# MOTOR_DRIVER_2.net
KiCad netlist of a schematic drawn in Altium Designer
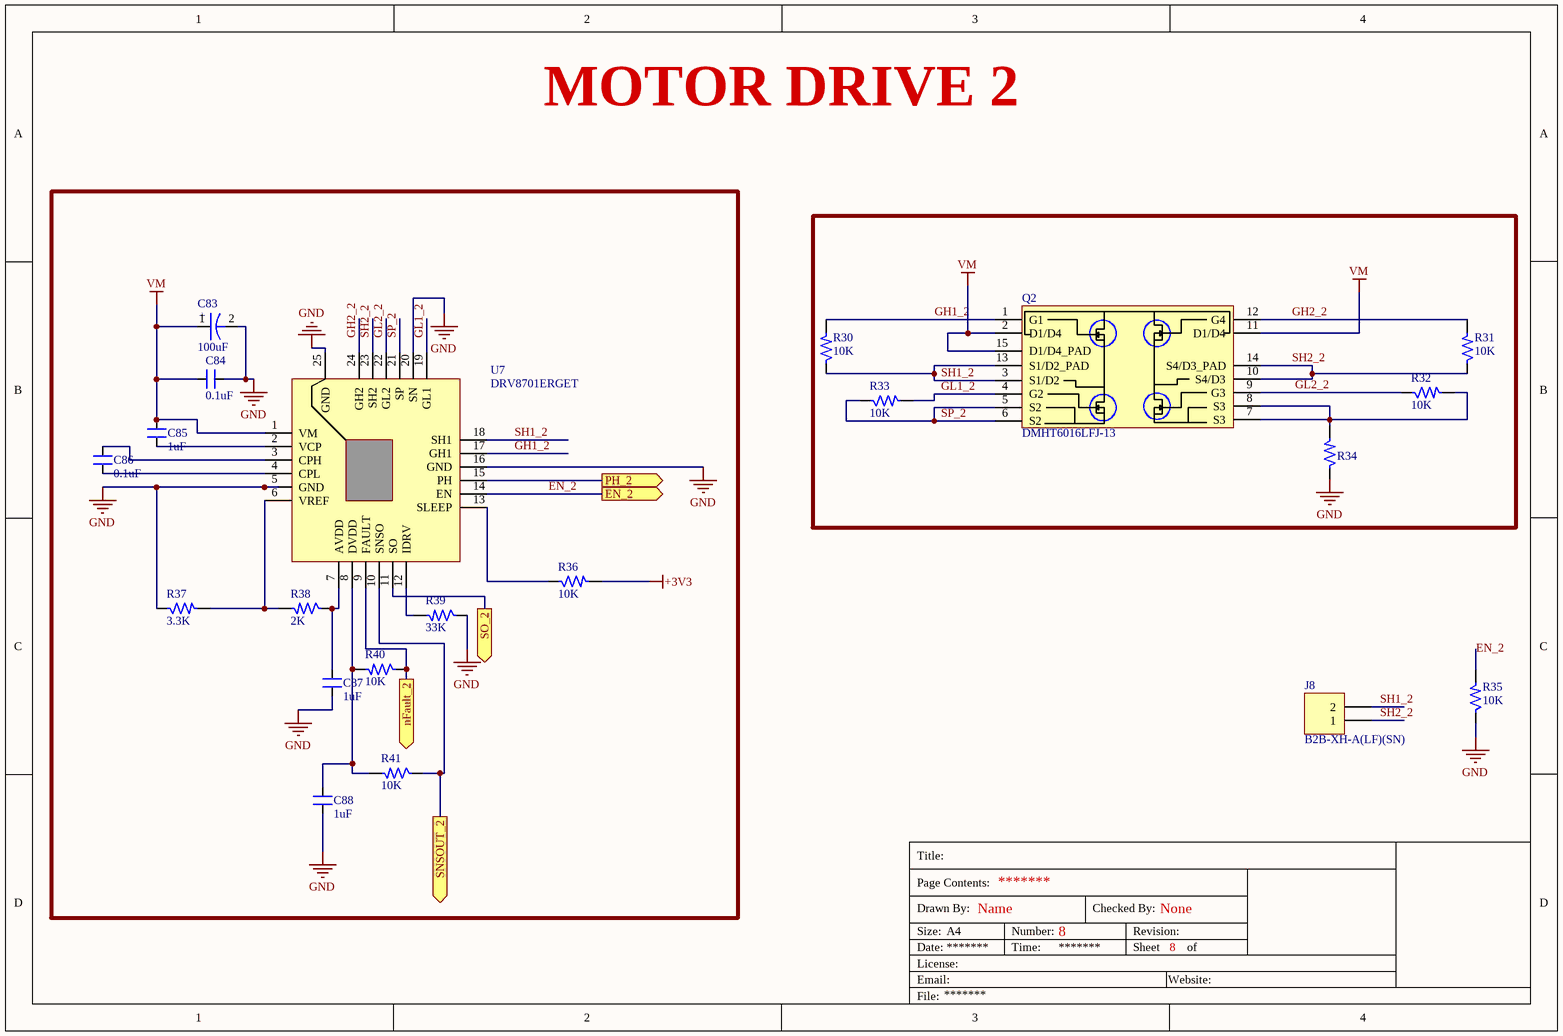
[diagram p0: MOTOR DRIVER 2.SchDoc]

(export (version "E")
  (design (tool "Eeschema 10.0.6"))
  (components
    (comp (ref "C83")
      (value "100uF")
      (footprint "ACAP_P236_D305_H303_RAD")
      (description "100µF 25V Aluminum Electrolytic Capacitors Radial, Can - SMD 1000 Hrs @ 105°C")
      (fields
        (field (name "MANUFACTURER") "Nichicon")
        (field (name "MANUFACTURER PART NUMBER") "UWT1E101MCL1GS")
      )
      (libsource (lib "ESTEEMPCBLIB") (part "CAP-P_100uF-25V-20%-RAD"))
    )
    (comp (ref "C84")
      (value "0.1uF")
      (footprint "CAP_0805")
      (description "0.1µF ±5% 50V Ceramic Capacitor X7R 0805 (2012 Metric)")
      (fields
        (field (name "MANUFACTURER") "AVX Corporation")
        (field (name "MANUFACTURER PART NUMBER") "08055C104JAT4A")
      )
      (libsource (lib "ESTEEMPCBLIB") (part "CAP_0.1uF-50V-5%-0805"))
    )
    (comp (ref "C85")
      (value "1uF")
      (footprint "CAP_0805")
      (description "1µF ±5% 50V Ceramic Capacitor X7R 0805 (2012 Metric)")
      (fields
        (field (name "MANUFACTURER") "Samsung")
        (field (name "MANUFACTURER PART NUMBER") "CC0805JKX7R9BB105")
      )
      (libsource (lib "ESTEEMPCBLIB") (part "CAP_1uF-50V-5%-0805"))
    )
    (comp (ref "C86")
      (value "0.1uF")
      (footprint "CAP_0805")
      (description "0.1µF ±5% 50V Ceramic Capacitor X7R 0805 (2012 Metric)")
      (fields
        (field (name "MANUFACTURER") "AVX Corporation")
        (field (name "MANUFACTURER PART NUMBER") "08055C104JAT4A")
      )
      (libsource (lib "ESTEEMPCBLIB") (part "CAP_0.1uF-50V-5%-0805"))
    )
    (comp (ref "C87")
      (value "1uF")
      (footprint "CAP_0805")
      (description "1µF ±5% 50V Ceramic Capacitor X7R 0805 (2012 Metric)")
      (fields
        (field (name "MANUFACTURER") "Samsung")
        (field (name "MANUFACTURER PART NUMBER") "CC0805JKX7R9BB105")
      )
      (libsource (lib "ESTEEMPCBLIB") (part "CAP_1uF-50V-5%-0805"))
    )
    (comp (ref "C88")
      (value "1uF")
      (footprint "CAP_0805")
      (description "1µF ±5% 50V Ceramic Capacitor X7R 0805 (2012 Metric)")
      (fields
        (field (name "MANUFACTURER") "Samsung")
        (field (name "MANUFACTURER PART NUMBER") "CC0805JKX7R9BB105")
      )
      (libsource (lib "ESTEEMPCBLIB") (part "CAP_1uF-50V-5%-0805"))
    )
    (comp (ref "J8")
      (value "B2B-XH-A(LF)(SN)")
      (footprint "CON2_100_B2B-XH-A_TH_ST")
      (description "2 Pins, 1 Row 2.54mm Pitch, Straight Connector, male")
      (fields (field (name "MANUFACTURER") "JST") (field (name "MATING PART NUMBER") "XHP-2"))
      (libsource (lib "ESTEEMPCBLIB") (part "CON-PLG_2X1-100-ST-TH"))
    )
    (comp (ref "Q2")
      (value "DMHT6016LFJ-13")
      (footprint "DFN5045-12_33_212_27X15_SMD_1")
      (description "Mosfet Array 4 N-Channel 14.8A (Ta) Surface Mount V-DFN5045-12")
      (fields (field (name "MANUFACTURER") "ON Semiconductor"))
      (libsource (lib "ESTEEMPCBLIB") (part "MOSFET-N_60V-14.8A-V-DFN5045-12"))
    )
    (comp (ref "R30")
      (value "10K")
      (footprint "RES_0805")
      (description "10 kOhms ±1% 0.125W, 1/8W Chip Resistor 0805 (2012 Metric) Automotive AEC-Q200 Thick Film")
      (fields (field (name "MANUFACTURER") "CTS") (field (name "MANUFACTURER PART NUMBER") "WR08X1002FTL"))
      (libsource (lib "ESTEEMPCBLIB") (part "RES_10K-0.125W-1%-0805"))
    )
    (comp (ref "R31")
      (value "10K")
      (footprint "RES_0805")
      (description "10 kOhms ±1% 0.125W, 1/8W Chip Resistor 0805 (2012 Metric) Automotive AEC-Q200 Thick Film")
      (fields (field (name "MANUFACTURER") "CTS") (field (name "MANUFACTURER PART NUMBER") "WR08X1002FTL"))
      (libsource (lib "ESTEEMPCBLIB") (part "RES_10K-0.125W-1%-0805"))
    )
    (comp (ref "R32")
      (value "10K")
      (footprint "RES_0805")
      (description "10 kOhms ±1% 0.125W, 1/8W Chip Resistor 0805 (2012 Metric) Automotive AEC-Q200 Thick Film")
      (fields (field (name "MANUFACTURER") "CTS") (field (name "MANUFACTURER PART NUMBER") "WR08X1002FTL"))
      (libsource (lib "ESTEEMPCBLIB") (part "RES_10K-0.125W-1%-0805"))
    )
    (comp (ref "R33")
      (value "10K")
      (footprint "RES_0805")
      (description "10 kOhms ±1% 0.125W, 1/8W Chip Resistor 0805 (2012 Metric) Automotive AEC-Q200 Thick Film")
      (fields (field (name "MANUFACTURER") "CTS") (field (name "MANUFACTURER PART NUMBER") "WR08X1002FTL"))
      (libsource (lib "ESTEEMPCBLIB") (part "RES_10K-0.125W-1%-0805"))
    )
    (comp (ref "R34")
      (value "RES_50mOHM-2W-2512 Current sense")
      (footprint "RESC6331X80N")
      (description "50 mOhms ±1% 2W Chip Resistor 2512 (6432 Metric) Current Sense Thick Film")
      (libsource (lib "ESTEEMPCBLIB") (part "RES_50mOHM-2W-2512 Current sense"))
    )
    (comp (ref "R35")
      (value "10K")
      (footprint "RES_0805")
      (description "10 kOhms ±1% 0.125W, 1/8W Chip Resistor 0805 (2012 Metric) Automotive AEC-Q200 Thick Film")
      (fields (field (name "MANUFACTURER") "CTS") (field (name "MANUFACTURER PART NUMBER") "WR08X1002FTL"))
      (libsource (lib "ESTEEMPCBLIB") (part "RES_10K-0.125W-1%-0805"))
    )
    (comp (ref "R36")
      (value "10K")
      (footprint "RES_0805")
      (description "10 kOhms ±1% 0.125W, 1/8W Chip Resistor 0805 (2012 Metric) Automotive AEC-Q200 Thick Film")
      (fields (field (name "MANUFACTURER") "CTS") (field (name "MANUFACTURER PART NUMBER") "WR08X1002FTL"))
      (libsource (lib "ESTEEMPCBLIB") (part "RES_10K-0.125W-1%-0805"))
    )
    (comp (ref "R37")
      (value "3.3K")
      (footprint "RES_0805")
      (description "3.3 kOhms ±1% 0.125W, 1/8W Chip Resistor 0805 (2012 Metric) Thick Film")
      (fields (field (name "MANUFACTURER") "Panasonic") (field (name "MANUFACTURER PART NUMBER") "1623214-1"))
      (libsource (lib "ESTEEMPCBLIB") (part "RES_3.3K-0.125W-1%-0805"))
    )
    (comp (ref "R38")
      (value "2K")
      (footprint "RES_0805")
      (description "2 kOhms ±1% 0.125W, 1/8W Chip Resistor 0805 (2012 Metric) Moisture Resistant Thick Film")
      (fields
        (field (name "MANUFACTURER") "TE Connectivity")
        (field (name "MANUFACTURER PART NUMBER") "RC0805FR-072KL")
      )
      (libsource (lib "ESTEEMPCBLIB") (part "RES_2K-0.125W-1%-0805"))
    )
    (comp (ref "R39")
      (value "33K")
      (footprint "RES_0805")
      (fields
        (field (name "MANUFACTURER") "Vishay BCcomponents")
        (field (name "MANUFACTURER PART NUMBER") "CRG0805F33K")
      )
      (libsource (lib "ESTEEMPCBLIB") (part "RES_33K-0.125W-1%-0805"))
    )
    (comp (ref "R40")
      (value "10K")
      (footprint "RES_0805")
      (description "10 kOhms ±1% 0.125W, 1/8W Chip Resistor 0805 (2012 Metric) Automotive AEC-Q200 Thick Film")
      (fields (field (name "MANUFACTURER") "CTS") (field (name "MANUFACTURER PART NUMBER") "WR08X1002FTL"))
      (libsource (lib "ESTEEMPCBLIB") (part "RES_10K-0.125W-1%-0805"))
    )
    (comp (ref "R41")
      (value "10K")
      (footprint "RES_0805")
      (description "10 kOhms ±1% 0.125W, 1/8W Chip Resistor 0805 (2012 Metric) Automotive AEC-Q200 Thick Film")
      (fields (field (name "MANUFACTURER") "CTS") (field (name "MANUFACTURER PART NUMBER") "WR08X1002FTL"))
      (libsource (lib "ESTEEMPCBLIB") (part "RES_10K-0.125W-1%-0805"))
    )
    (comp (ref "U7")
      (value "DRV8701ERGET")
      (footprint "VFQFN24_19.6_196_12X32_SMD_1")
      (description "Motor Driver Power MOSFET Parallel 24-VQFN (4x4)")
      (fields (field (name "MANUFACTURER") "Texas Instruments"))
      (libsource (lib "ESTEEMPCBLIB") (part "IC_DRV8701ERGET"))
    )
  )
  (nets
    (net (code "1") (name "+3V3") (class "Default")
      (node (ref "R36") (pin "2") (pinfunction "2_2") (pintype "passive"))
    )
    (net (code "2") (name "/EN_2") (class "Default")
      (node (ref "R35") (pin "2") (pinfunction "2_2") (pintype "passive"))
      (node (ref "U7") (pin "14") (pinfunction "EN_14") (pintype "passive"))
    )
    (net (code "3") (name "/GH1_2") (class "Default")
      (node (ref "Q2") (pin "1") (pinfunction "G1_1") (pintype "passive"))
      (node (ref "R30") (pin "2") (pinfunction "2_2") (pintype "passive"))
      (node (ref "U7") (pin "17") (pinfunction "GH1_17") (pintype "passive"))
    )
    (net (code "4") (name "/GH2_2") (class "Default")
      (node (ref "Q2") (pin "12") (pinfunction "G4_12") (pintype "passive"))
      (node (ref "R31") (pin "2") (pinfunction "2_2") (pintype "passive"))
      (node (ref "U7") (pin "24") (pinfunction "GH2_24") (pintype "passive"))
    )
    (net (code "5") (name "/GL1_2") (class "Default")
      (node (ref "Q2") (pin "4") (pinfunction "G2_4") (pintype "passive"))
      (node (ref "R33") (pin "2") (pinfunction "2_2") (pintype "passive"))
      (node (ref "U7") (pin "19") (pinfunction "GL1_19") (pintype "passive"))
    )
    (net (code "6") (name "/GL2_2") (class "Default")
      (node (ref "Q2") (pin "9") (pinfunction "G3_9") (pintype "passive"))
      (node (ref "R32") (pin "1") (pinfunction "1_1") (pintype "passive"))
      (node (ref "U7") (pin "22") (pinfunction "GL2_22") (pintype "passive"))
    )
    (net (code "7") (name "/PH_2") (class "Default")
      (node (ref "U7") (pin "15") (pinfunction "PH_15") (pintype "passive"))
    )
    (net (code "8") (name "/SH1_2") (class "Default")
      (node (ref "J8") (pin "2") (pinfunction "2_2") (pintype "passive"))
      (node (ref "Q2") (pin "13") (pinfunction "S1/D2_PAD_13") (pintype "passive"))
      (node (ref "Q2") (pin "3") (pinfunction "S1/D2_3") (pintype "passive"))
      (node (ref "R30") (pin "1") (pinfunction "1_1") (pintype "passive"))
      (node (ref "U7") (pin "18") (pinfunction "SH1_18") (pintype "passive"))
    )
    (net (code "9") (name "/SH2_2") (class "Default")
      (node (ref "J8") (pin "1") (pinfunction "1_1") (pintype "passive"))
      (node (ref "Q2") (pin "10") (pinfunction "S4/D3_10") (pintype "passive"))
      (node (ref "Q2") (pin "14") (pinfunction "S4/D3_PAD_14") (pintype "passive"))
      (node (ref "R31") (pin "1") (pinfunction "1_1") (pintype "passive"))
      (node (ref "U7") (pin "23") (pinfunction "SH2_23") (pintype "passive"))
    )
    (net (code "10") (name "/SNSOUT_2") (class "Default")
      (node (ref "R41") (pin "1") (pinfunction "1_1") (pintype "passive"))
      (node (ref "U7") (pin "10") (pinfunction "SNSO_10") (pintype "passive"))
    )
    (net (code "11") (name "/SO_2") (class "Default")
      (node (ref "U7") (pin "11") (pinfunction "SO_11") (pintype "passive"))
    )
    (net (code "12") (name "/SP_2") (class "Default")
      (node (ref "Q2") (pin "5") (pinfunction "S2_5") (pintype "passive"))
      (node (ref "Q2") (pin "6") (pinfunction "S2_6") (pintype "passive"))
      (node (ref "R33") (pin "1") (pinfunction "1_1") (pintype "passive"))
      (node (ref "U7") (pin "21") (pinfunction "SP_21") (pintype "passive"))
    )
    (net (code "13") (name "/nFault_2") (class "Default")
      (node (ref "R40") (pin "1") (pinfunction "1_1") (pintype "passive"))
      (node (ref "U7") (pin "9") (pinfunction "FAULT_9") (pintype "passive"))
    )
    (net (code "14") (name "GND") (class "Default")
      (node (ref "C83") (pin "2") (pinfunction "2_2") (pintype "passive"))
      (node (ref "C84") (pin "2") (pinfunction "2_2") (pintype "passive"))
      (node (ref "C87") (pin "1") (pinfunction "1_1") (pintype "passive"))
      (node (ref "C88") (pin "1") (pinfunction "1_1") (pintype "passive"))
      (node (ref "R34") (pin "1") (pinfunction "1_1") (pintype "passive"))
      (node (ref "R35") (pin "1") (pinfunction "1_1") (pintype "passive"))
      (node (ref "R37") (pin "1") (pinfunction "1_1") (pintype "passive"))
      (node (ref "R39") (pin "1") (pinfunction "1_1") (pintype "passive"))
      (node (ref "U7") (pin "16") (pinfunction "GND_16") (pintype "passive"))
      (node (ref "U7") (pin "20") (pinfunction "SN_20") (pintype "passive"))
      (node (ref "U7") (pin "25") (pinfunction "GND_25") (pintype "passive"))
      (node (ref "U7") (pin "5") (pinfunction "GND_5") (pintype "passive"))
    )
    (net (code "15") (name "Net-(Q2-S3-Pad7)") (class "Default")
      (node (ref "Q2") (pin "7") (pinfunction "S3_7") (pintype "passive"))
      (node (ref "Q2") (pin "8") (pinfunction "S3_8") (pintype "passive"))
      (node (ref "R32") (pin "2") (pinfunction "2_2") (pintype "passive"))
      (node (ref "R34") (pin "2") (pinfunction "2_2") (pintype "passive"))
    )
    (net (code "16") (name "Net-(U7-AVDD)") (class "Default")
      (node (ref "C87") (pin "2") (pinfunction "2_2") (pintype "passive"))
      (node (ref "R38") (pin "1") (pinfunction "1_1") (pintype "passive"))
      (node (ref "U7") (pin "7") (pinfunction "AVDD_7") (pintype "passive"))
    )
    (net (code "17") (name "Net-(U7-CPH)") (class "Default")
      (node (ref "C86") (pin "2") (pinfunction "2_2") (pintype "passive"))
      (node (ref "U7") (pin "3") (pinfunction "CPH_3") (pintype "passive"))
    )
    (net (code "18") (name "Net-(U7-CPL)") (class "Default")
      (node (ref "C86") (pin "1") (pinfunction "1_1") (pintype "passive"))
      (node (ref "U7") (pin "4") (pinfunction "CPL_4") (pintype "passive"))
    )
    (net (code "19") (name "Net-(U7-DVDD)") (class "Default")
      (node (ref "C88") (pin "2") (pinfunction "2_2") (pintype "passive"))
      (node (ref "R40") (pin "2") (pinfunction "2_2") (pintype "passive"))
      (node (ref "R41") (pin "2") (pinfunction "2_2") (pintype "passive"))
      (node (ref "U7") (pin "8") (pinfunction "DVDD_8") (pintype "passive"))
    )
    (net (code "20") (name "Net-(U7-IDRV)") (class "Default")
      (node (ref "R39") (pin "2") (pinfunction "2_2") (pintype "passive"))
      (node (ref "U7") (pin "12") (pinfunction "IDRV_12") (pintype "passive"))
    )
    (net (code "21") (name "Net-(U7-SLEEP)") (class "Default")
      (node (ref "R36") (pin "1") (pinfunction "1_1") (pintype "passive"))
      (node (ref "U7") (pin "13") (pinfunction "SLEEP_13") (pintype "passive"))
    )
    (net (code "22") (name "Net-(U7-VCP)") (class "Default")
      (node (ref "C85") (pin "1") (pinfunction "1_1") (pintype "passive"))
      (node (ref "U7") (pin "2") (pinfunction "VCP_2") (pintype "passive"))
    )
    (net (code "23") (name "Net-(U7-VREF)") (class "Default")
      (node (ref "R37") (pin "2") (pinfunction "2_2") (pintype "passive"))
      (node (ref "R38") (pin "2") (pinfunction "2_2") (pintype "passive"))
      (node (ref "U7") (pin "6") (pinfunction "VREF_6") (pintype "passive"))
    )
    (net (code "24") (name "VM") (class "Default")
      (node (ref "C83") (pin "1") (pinfunction "1_1") (pintype "passive"))
      (node (ref "C84") (pin "1") (pinfunction "1_1") (pintype "passive"))
      (node (ref "C85") (pin "2") (pinfunction "2_2") (pintype "passive"))
      (node (ref "Q2") (pin "11") (pinfunction "D1/D4_11") (pintype "passive"))
      (node (ref "Q2") (pin "15") (pinfunction "D1/D4_PAD_15") (pintype "passive"))
      (node (ref "Q2") (pin "2") (pinfunction "D1/D4_2") (pintype "passive"))
      (node (ref "U7") (pin "1") (pinfunction "VM_1") (pintype "passive"))
    )
  )
)
